# CircularDisplayPrototypingBoard.net
KiCad netlist of a schematic drawn in EAGLE
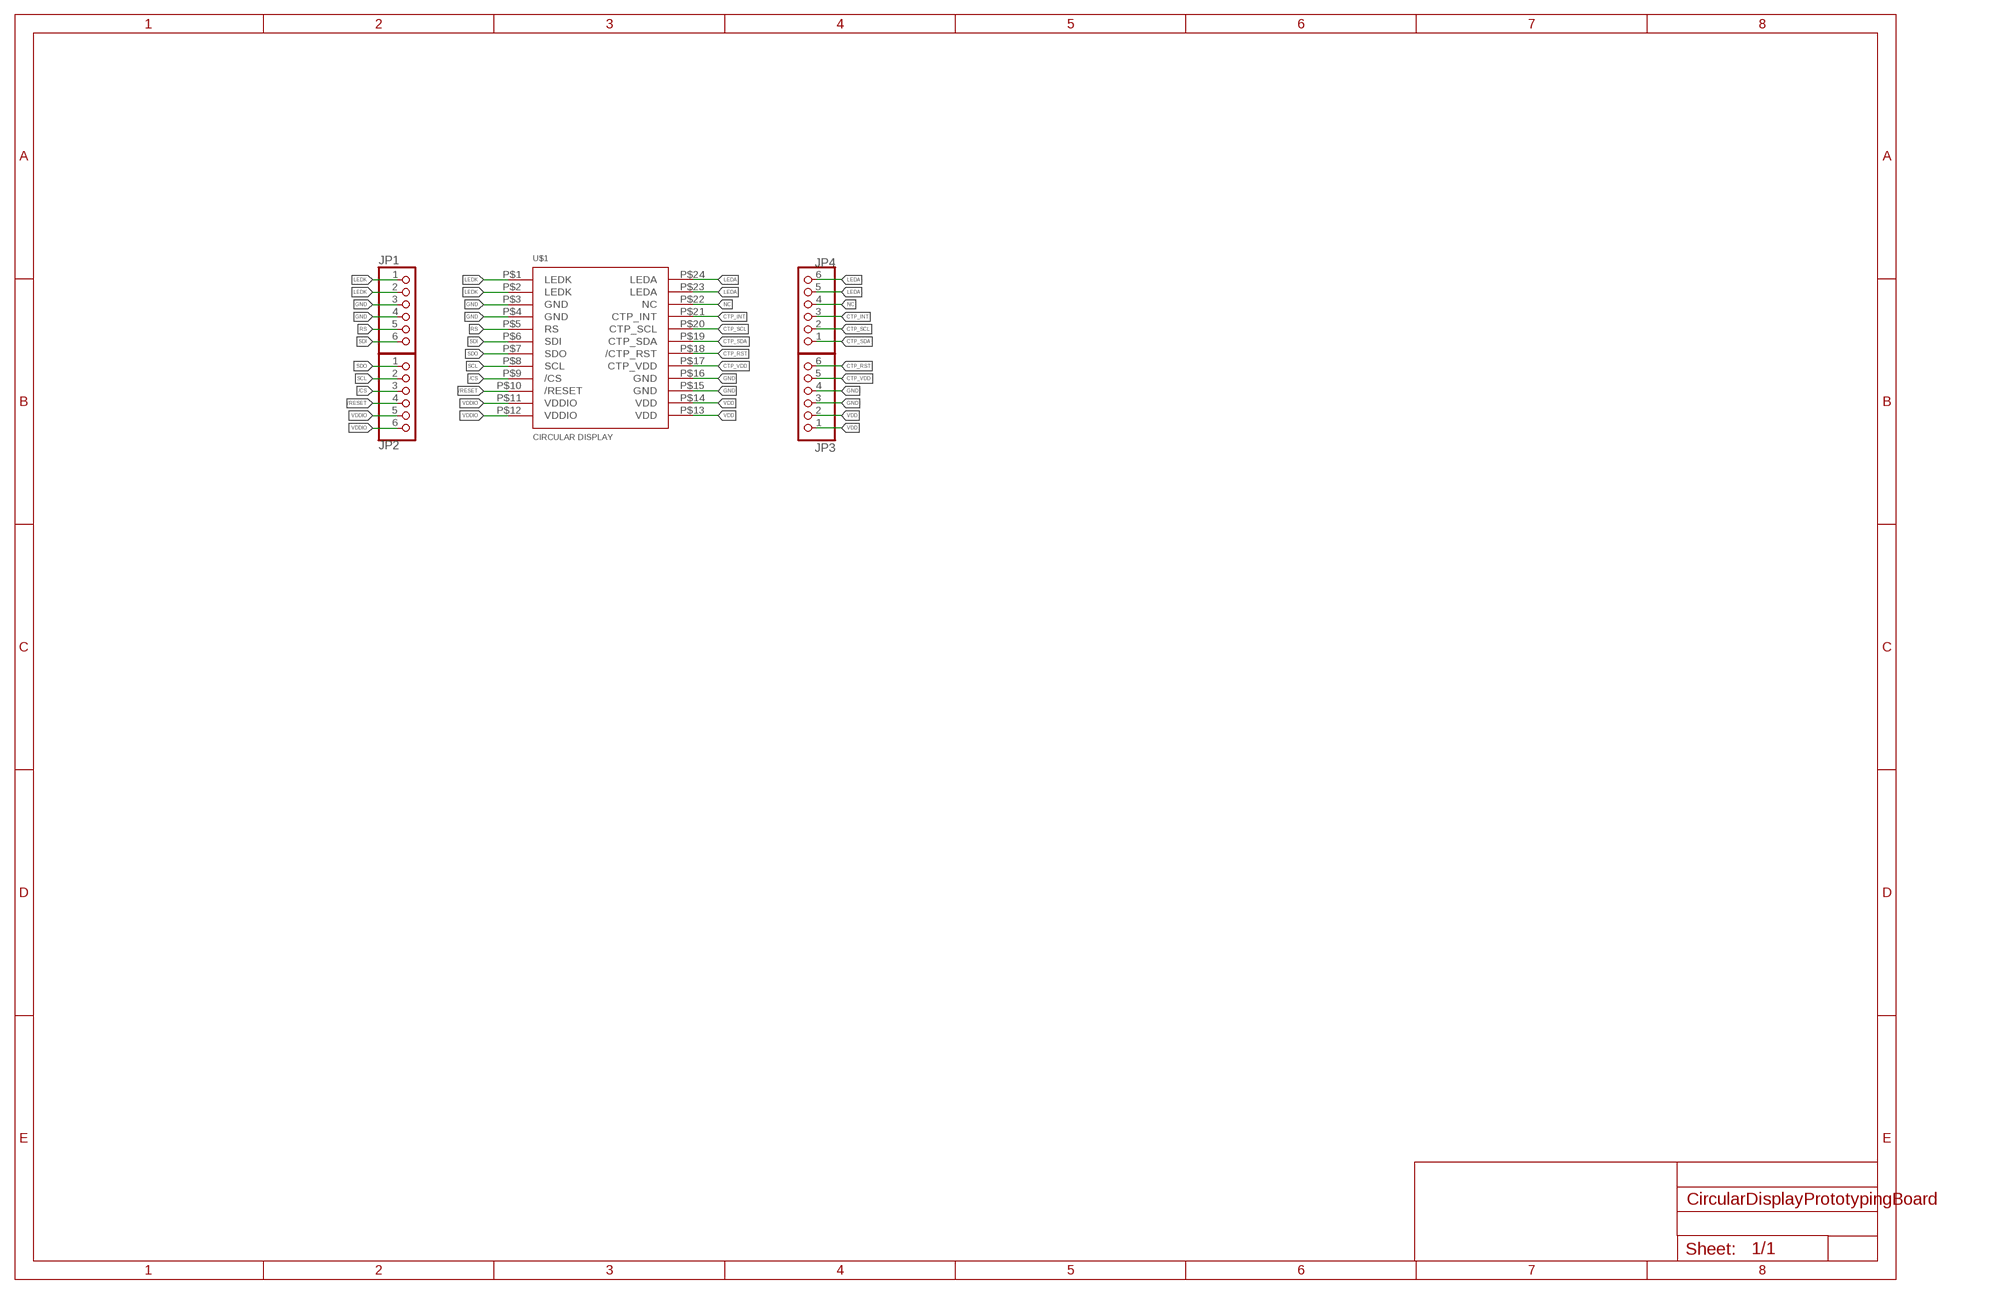
[diagram p0: schematic, sheet 1]

(export (version "E")
  (design (tool "Eeschema 10.0.6"))
  (components
    (comp (ref "JP1")
      (value "PINHD-1X6")
      (footprint "eagle-import:1X06")
      (libsource (lib "eagle-import") (part "PINHD-1X6"))
    )
    (comp (ref "JP2")
      (value "PINHD-1X6")
      (footprint "eagle-import:1X06")
      (libsource (lib "eagle-import") (part "PINHD-1X6"))
    )
    (comp (ref "JP3")
      (value "PINHD-1X6")
      (footprint "eagle-import:1X06")
      (libsource (lib "eagle-import") (part "PINHD-1X6"))
    )
    (comp (ref "JP4")
      (value "PINHD-1X6")
      (footprint "eagle-import:1X06")
      (libsource (lib "eagle-import") (part "PINHD-1X6"))
    )
    (comp (ref "U$1")
      (value "CIRCULAR-DISPLAY-1")
      (footprint "eagle-import:CIRCULAR-DISPLAY-1")
      (libsource (lib "eagle-import") (part "CIRCULAR-DISPLAY-1"))
    )
  )
  (nets
    (net (code "1") (name "CTP_INT") (class "Default")
      (node (ref "JP4") (pin "3") (pinfunction "3_3") (pintype "passive"))
      (node (ref "U$1") (pin "P$21") (pinfunction "CTP_INT_P$21") (pintype "bidirectional"))
    )
    (net (code "2") (name "CTP_RST") (class "Default")
      (node (ref "JP3") (pin "6") (pinfunction "6_6") (pintype "passive"))
      (node (ref "U$1") (pin "P$18") (pinfunction "/CTP_RST_P$18") (pintype "bidirectional"))
    )
    (net (code "3") (name "CTP_SCL") (class "Default")
      (node (ref "JP4") (pin "2") (pinfunction "2_2") (pintype "passive"))
      (node (ref "U$1") (pin "P$20") (pinfunction "CTP_SCL_P$20") (pintype "bidirectional"))
    )
    (net (code "4") (name "CTP_SDA") (class "Default")
      (node (ref "JP4") (pin "1") (pinfunction "1_1") (pintype "passive"))
      (node (ref "U$1") (pin "P$19") (pinfunction "CTP_SDA_P$19") (pintype "bidirectional"))
    )
    (net (code "5") (name "CTP_VDD") (class "Default")
      (node (ref "JP3") (pin "5") (pinfunction "5_5") (pintype "passive"))
      (node (ref "U$1") (pin "P$17") (pinfunction "CTP_VDD_P$17") (pintype "bidirectional"))
    )
    (net (code "6") (name "GND") (class "Default")
      (node (ref "JP1") (pin "3") (pinfunction "3_3") (pintype "passive"))
      (node (ref "JP1") (pin "4") (pinfunction "4_4") (pintype "passive"))
      (node (ref "JP3") (pin "3") (pinfunction "3_3") (pintype "passive"))
      (node (ref "JP3") (pin "4") (pinfunction "4_4") (pintype "passive"))
      (node (ref "U$1") (pin "P$15") (pinfunction "GND_P$15") (pintype "bidirectional"))
      (node (ref "U$1") (pin "P$16") (pinfunction "GND_P$16") (pintype "bidirectional"))
      (node (ref "U$1") (pin "P$3") (pinfunction "GND_P$3") (pintype "bidirectional"))
      (node (ref "U$1") (pin "P$4") (pinfunction "GND_P$4") (pintype "bidirectional"))
    )
    (net (code "7") (name "LEDA") (class "Default")
      (node (ref "JP4") (pin "5") (pinfunction "5_5") (pintype "passive"))
      (node (ref "JP4") (pin "6") (pinfunction "6_6") (pintype "passive"))
      (node (ref "U$1") (pin "P$23") (pinfunction "LEDA_P$23") (pintype "bidirectional"))
      (node (ref "U$1") (pin "P$24") (pinfunction "LEDA_P$24") (pintype "bidirectional"))
    )
    (net (code "8") (name "LEDK") (class "Default")
      (node (ref "JP1") (pin "1") (pinfunction "1_1") (pintype "passive"))
      (node (ref "JP1") (pin "2") (pinfunction "2_2") (pintype "passive"))
      (node (ref "U$1") (pin "P$1") (pinfunction "LEDK_P$1") (pintype "bidirectional"))
      (node (ref "U$1") (pin "P$2") (pinfunction "LEDK_P$2") (pintype "bidirectional"))
    )
    (net (code "9") (name "NC") (class "Default")
      (node (ref "JP4") (pin "4") (pinfunction "4_4") (pintype "passive"))
      (node (ref "U$1") (pin "P$22") (pinfunction "NC_P$22") (pintype "bidirectional"))
    )
    (net (code "10") (name "RS") (class "Default")
      (node (ref "JP1") (pin "5") (pinfunction "5_5") (pintype "passive"))
      (node (ref "U$1") (pin "P$5") (pinfunction "RS_P$5") (pintype "bidirectional"))
    )
    (net (code "11") (name "SCL") (class "Default")
      (node (ref "JP2") (pin "2") (pinfunction "2_2") (pintype "passive"))
      (node (ref "U$1") (pin "P$8") (pinfunction "SCL_P$8") (pintype "bidirectional"))
    )
    (net (code "12") (name "SDI") (class "Default")
      (node (ref "JP1") (pin "6") (pinfunction "6_6") (pintype "passive"))
      (node (ref "U$1") (pin "P$6") (pinfunction "SDI_P$6") (pintype "bidirectional"))
    )
    (net (code "13") (name "SDO") (class "Default")
      (node (ref "JP2") (pin "1") (pinfunction "1_1") (pintype "passive"))
      (node (ref "U$1") (pin "P$7") (pinfunction "SDO_P$7") (pintype "bidirectional"))
    )
    (net (code "14") (name "VDD") (class "Default")
      (node (ref "JP3") (pin "1") (pinfunction "1_1") (pintype "passive"))
      (node (ref "JP3") (pin "2") (pinfunction "2_2") (pintype "passive"))
      (node (ref "U$1") (pin "P$13") (pinfunction "VDD_P$13") (pintype "bidirectional"))
      (node (ref "U$1") (pin "P$14") (pinfunction "VDD_P$14") (pintype "bidirectional"))
    )
    (net (code "15") (name "VDDIO") (class "Default")
      (node (ref "JP2") (pin "5") (pinfunction "5_5") (pintype "passive"))
      (node (ref "JP2") (pin "6") (pinfunction "6_6") (pintype "passive"))
      (node (ref "U$1") (pin "P$11") (pinfunction "VDDIO_P$11") (pintype "bidirectional"))
      (node (ref "U$1") (pin "P$12") (pinfunction "VDDIO_P$12") (pintype "bidirectional"))
    )
    (net (code "16") (name "{slash}CS") (class "Default")
      (node (ref "JP2") (pin "3") (pinfunction "3_3") (pintype "passive"))
      (node (ref "U$1") (pin "P$9") (pinfunction "/CS_P$9") (pintype "bidirectional"))
    )
    (net (code "17") (name "{slash}RESET") (class "Default")
      (node (ref "JP2") (pin "4") (pinfunction "4_4") (pintype "passive"))
      (node (ref "U$1") (pin "P$10") (pinfunction "/RESET_P$10") (pintype "bidirectional"))
    )
  )
)
